# Pure_Noise.net
KiCad netlist of a schematic drawn in EAGLE
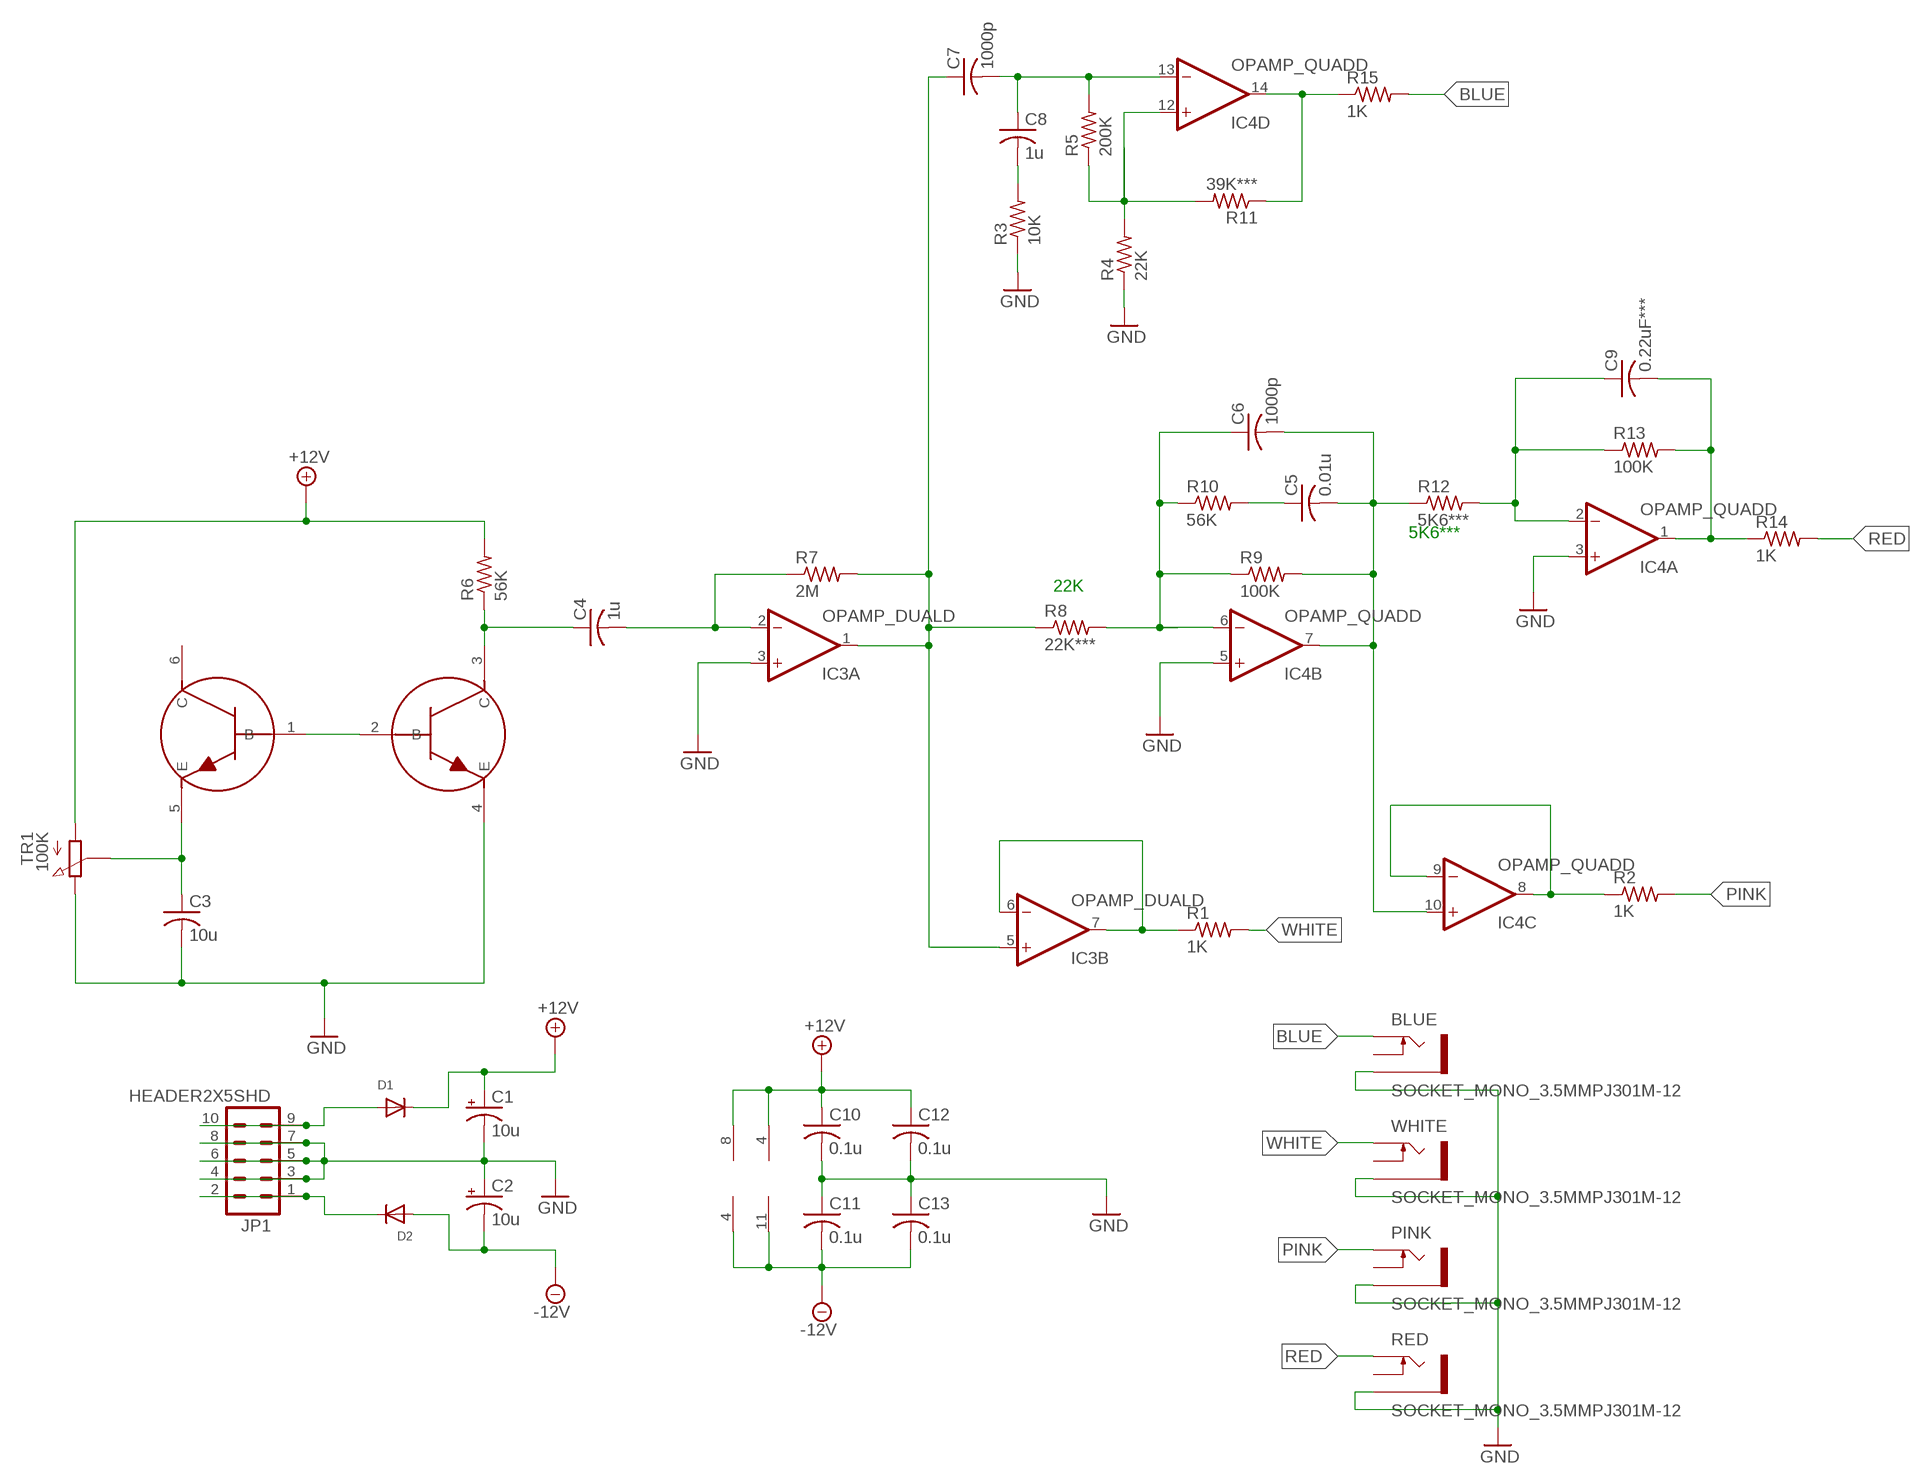
[diagram p0: schematic, sheet 1]

(export (version "E")
  (design (tool "Eeschema 10.0.6"))
  (components
    (comp (ref "BLUE")
      (value "SOCKET_MONO_3.5MMPJ301M-12")
      (footprint "eagle-import:PJ301M-12")
      (libsource (lib "eagle-import") (part "SOCKET_MONO_3.5MMPJ301M-12"))
    )
    (comp (ref "C1")
      (value "10u")
      (footprint "eagle-import:153CLV-0505")
      (libsource (lib "eagle-import") (part "CAPACITOR_POL-US153CLV-0505"))
    )
    (comp (ref "C2")
      (value "10u")
      (footprint "eagle-import:153CLV-0505")
      (libsource (lib "eagle-import") (part "CAPACITOR_POL-US153CLV-0505"))
    )
    (comp (ref "C3")
      (value "10u")
      (footprint "eagle-import:C0805")
      (libsource (lib "eagle-import") (part "CAPACITOR-USC0805"))
    )
    (comp (ref "C4")
      (value "1u")
      (footprint "eagle-import:C0805")
      (libsource (lib "eagle-import") (part "CAPACITOR-USC0805"))
    )
    (comp (ref "C5")
      (value "0.01u")
      (footprint "eagle-import:C0805")
      (libsource (lib "eagle-import") (part "CAPACITOR-USC0805"))
    )
    (comp (ref "C6")
      (value "1000p")
      (footprint "eagle-import:C0805")
      (libsource (lib "eagle-import") (part "CAPACITOR-USC0805"))
    )
    (comp (ref "C7")
      (value "1000p")
      (footprint "eagle-import:C0805")
      (libsource (lib "eagle-import") (part "CAPACITOR-USC0805"))
    )
    (comp (ref "C8")
      (value "1u")
      (footprint "eagle-import:C0805")
      (libsource (lib "eagle-import") (part "CAPACITOR-USC0805"))
    )
    (comp (ref "C9")
      (value "0.22uF***")
      (footprint "eagle-import:C0805")
      (libsource (lib "eagle-import") (part "CAPACITOR-USC0805"))
    )
    (comp (ref "C10")
      (value "0.1u")
      (footprint "eagle-import:C0805")
      (libsource (lib "eagle-import") (part "CAPACITOR-USC0805"))
    )
    (comp (ref "C11")
      (value "0.1u")
      (footprint "eagle-import:C0805")
      (libsource (lib "eagle-import") (part "CAPACITOR-USC0805"))
    )
    (comp (ref "C12")
      (value "0.1u")
      (footprint "eagle-import:C0805")
      (libsource (lib "eagle-import") (part "CAPACITOR-USC0805"))
    )
    (comp (ref "C13")
      (value "0.1u")
      (footprint "eagle-import:C0805")
      (libsource (lib "eagle-import") (part "CAPACITOR-USC0805"))
    )
    (comp (ref "D1")
      (value "DIODESMA")
      (footprint "eagle-import:SMADIODE")
      (libsource (lib "eagle-import") (part "DIODESMA"))
    )
    (comp (ref "D2")
      (value "DIODESMA")
      (footprint "eagle-import:SMADIODE")
      (libsource (lib "eagle-import") (part "DIODESMA"))
    )
    (comp (ref "IC3")
      (value "OPAMP_DUALD")
      (footprint "eagle-import:SO08")
      (libsource (lib "eagle-import") (part "OPAMP_DUALD"))
    )
    (comp (ref "IC4")
      (value "OPAMP_QUADD")
      (footprint "eagle-import:SO14")
      (libsource (lib "eagle-import") (part "OPAMP_QUADD"))
    )
    (comp (ref "JP1")
      (value "HEADER2X5SHD")
      (footprint "eagle-import:2X5-SHROUDED")
      (libsource (lib "eagle-import") (part "HEADER2X5SHD"))
    )
    (comp (ref "PINK")
      (value "SOCKET_MONO_3.5MMPJ301M-12")
      (footprint "eagle-import:PJ301M-12")
      (libsource (lib "eagle-import") (part "SOCKET_MONO_3.5MMPJ301M-12"))
    )
    (comp (ref "R1")
      (value "1K")
      (footprint "eagle-import:R0805")
      (libsource (lib "eagle-import") (part "RESISTOR_USR0805"))
    )
    (comp (ref "R2")
      (value "1K")
      (footprint "eagle-import:R0805")
      (libsource (lib "eagle-import") (part "RESISTOR_USR0805"))
    )
    (comp (ref "R3")
      (value "10K")
      (footprint "eagle-import:R0805")
      (libsource (lib "eagle-import") (part "RESISTOR_USR0805"))
    )
    (comp (ref "R4")
      (value "22K")
      (footprint "eagle-import:R0805")
      (libsource (lib "eagle-import") (part "RESISTOR_USR0805"))
    )
    (comp (ref "R5")
      (value "200K")
      (footprint "eagle-import:R0805")
      (libsource (lib "eagle-import") (part "RESISTOR_USR0805"))
    )
    (comp (ref "R6")
      (value "56K")
      (footprint "eagle-import:R0805")
      (libsource (lib "eagle-import") (part "RESISTOR_USR0805"))
    )
    (comp (ref "R7")
      (value "2M")
      (footprint "eagle-import:R0805")
      (libsource (lib "eagle-import") (part "RESISTOR_USR0805"))
    )
    (comp (ref "R8")
      (value "22K***")
      (footprint "eagle-import:R0805")
      (libsource (lib "eagle-import") (part "RESISTOR_USR0805"))
    )
    (comp (ref "R9")
      (value "100K")
      (footprint "eagle-import:R0805")
      (libsource (lib "eagle-import") (part "RESISTOR_USR0805"))
    )
    (comp (ref "R10")
      (value "56K")
      (footprint "eagle-import:R0805")
      (libsource (lib "eagle-import") (part "RESISTOR_USR0805"))
    )
    (comp (ref "R11")
      (value "39K***")
      (footprint "eagle-import:R0805")
      (libsource (lib "eagle-import") (part "RESISTOR_USR0805"))
    )
    (comp (ref "R12")
      (value "5K6***")
      (footprint "eagle-import:R0805")
      (libsource (lib "eagle-import") (part "RESISTOR_USR0805"))
    )
    (comp (ref "R13")
      (value "100K")
      (footprint "eagle-import:R0805")
      (libsource (lib "eagle-import") (part "RESISTOR_USR0805"))
    )
    (comp (ref "R14")
      (value "1K")
      (footprint "eagle-import:R0805")
      (libsource (lib "eagle-import") (part "RESISTOR_USR0805"))
    )
    (comp (ref "R15")
      (value "1K")
      (footprint "eagle-import:R0805")
      (libsource (lib "eagle-import") (part "RESISTOR_USR0805"))
    )
    (comp (ref "RED")
      (value "SOCKET_MONO_3.5MMPJ301M-12")
      (footprint "eagle-import:PJ301M-12")
      (libsource (lib "eagle-import") (part "SOCKET_MONO_3.5MMPJ301M-12"))
    )
    (comp (ref "T1")
      (value "TRANSISTOR_PAIR_NPN")
      (footprint "eagle-import:TRANS_PAIR")
      (libsource (lib "eagle-import") (part "TRANSISTOR_PAIR_NPN"))
    )
    (comp (ref "TR1")
      (value "100K")
      (footprint "eagle-import:TRIMMER_TH")
      (libsource (lib "eagle-import") (part "RESISTOR_VARIABLETRIMMER_TH"))
    )
    (comp (ref "WHITE")
      (value "SOCKET_MONO_3.5MMPJ301M-12")
      (footprint "eagle-import:PJ301M-12")
      (libsource (lib "eagle-import") (part "SOCKET_MONO_3.5MMPJ301M-12"))
    )
  )
  (nets
    (net (code "1") (name "+12V") (class "Default")
      (node (ref "C1") (pin "+") (pinfunction "+_+") (pintype "passive"))
      (node (ref "C10") (pin "1") (pinfunction "1_1") (pintype "passive"))
      (node (ref "C12") (pin "1") (pinfunction "1_1") (pintype "passive"))
      (node (ref "D1") (pin "C") (pinfunction "C_C") (pintype "passive"))
      (node (ref "IC3") (pin "8") (pinfunction "V+_8") (pintype "power_in"))
      (node (ref "IC4") (pin "4") (pinfunction "V+_4") (pintype "power_in"))
      (node (ref "R6") (pin "2") (pinfunction "2_2") (pintype "passive"))
      (node (ref "TR1") (pin "1") (pinfunction "1_1") (pintype "passive"))
    )
    (net (code "2") (name "-12V") (class "Default")
      (node (ref "C11") (pin "2") (pinfunction "2_2") (pintype "passive"))
      (node (ref "C13") (pin "2") (pinfunction "2_2") (pintype "passive"))
      (node (ref "C2") (pin "-") (pinfunction "-_-") (pintype "passive"))
      (node (ref "D2") (pin "A") (pinfunction "A_A") (pintype "passive"))
      (node (ref "IC3") (pin "4") (pinfunction "V-_4") (pintype "power_in"))
      (node (ref "IC4") (pin "11") (pinfunction "V-_11") (pintype "power_in"))
    )
    (net (code "3") (name "BLUE") (class "Default")
      (node (ref "BLUE") (pin "TIP") (pinfunction "TIP_TIP") (pintype "passive"))
      (node (ref "R15") (pin "2") (pinfunction "2_2") (pintype "passive"))
    )
    (net (code "4") (name "GND") (class "Default")
      (node (ref "BLUE") (pin "GND") (pinfunction "SLEEVE_GND") (pintype "passive"))
      (node (ref "C1") (pin "-") (pinfunction "-_-") (pintype "passive"))
      (node (ref "C10") (pin "2") (pinfunction "2_2") (pintype "passive"))
      (node (ref "C11") (pin "1") (pinfunction "1_1") (pintype "passive"))
      (node (ref "C12") (pin "2") (pinfunction "2_2") (pintype "passive"))
      (node (ref "C13") (pin "1") (pinfunction "1_1") (pintype "passive"))
      (node (ref "C2") (pin "+") (pinfunction "+_+") (pintype "passive"))
      (node (ref "C3") (pin "2") (pinfunction "2_2") (pintype "passive"))
      (node (ref "IC3") (pin "3") (pinfunction "+IN_3") (pintype "input"))
      (node (ref "IC4") (pin "3") (pinfunction "+IN_3") (pintype "input"))
      (node (ref "IC4") (pin "5") (pinfunction "+IN_5") (pintype "input"))
      (node (ref "JP1") (pin "3") (pinfunction "3_3") (pintype "passive"))
      (node (ref "JP1") (pin "4") (pinfunction "4_4") (pintype "passive"))
      (node (ref "JP1") (pin "5") (pinfunction "5_5") (pintype "passive"))
      (node (ref "JP1") (pin "6") (pinfunction "6_6") (pintype "passive"))
      (node (ref "JP1") (pin "7") (pinfunction "7_7") (pintype "passive"))
      (node (ref "JP1") (pin "8") (pinfunction "8_8") (pintype "passive"))
      (node (ref "PINK") (pin "GND") (pinfunction "SLEEVE_GND") (pintype "passive"))
      (node (ref "R3") (pin "1") (pinfunction "1_1") (pintype "passive"))
      (node (ref "R4") (pin "1") (pinfunction "1_1") (pintype "passive"))
      (node (ref "RED") (pin "GND") (pinfunction "SLEEVE_GND") (pintype "passive"))
      (node (ref "T1") (pin "4") (pinfunction "E_4") (pintype "bidirectional"))
      (node (ref "TR1") (pin "3") (pinfunction "3_3") (pintype "passive"))
      (node (ref "WHITE") (pin "GND") (pinfunction "SLEEVE_GND") (pintype "passive"))
    )
    (net (code "5") (name "Net-(C5-Pad1)") (class "Default")
      (node (ref "C5") (pin "1") (pinfunction "1_1") (pintype "passive"))
      (node (ref "R10") (pin "2") (pinfunction "2_2") (pintype "passive"))
    )
    (net (code "6") (name "Net-(C8-Pad2)") (class "Default")
      (node (ref "C8") (pin "2") (pinfunction "2_2") (pintype "passive"))
      (node (ref "R3") (pin "2") (pinfunction "2_2") (pintype "passive"))
    )
    (net (code "7") (name "Net-(D1-PadA)") (class "Default")
      (node (ref "D1") (pin "A") (pinfunction "A_A") (pintype "passive"))
      (node (ref "JP1") (pin "10") (pinfunction "10_10") (pintype "passive"))
      (node (ref "JP1") (pin "9") (pinfunction "9_9") (pintype "passive"))
    )
    (net (code "8") (name "Net-(D2-PadC)") (class "Default")
      (node (ref "D2") (pin "C") (pinfunction "C_C") (pintype "passive"))
      (node (ref "JP1") (pin "1") (pinfunction "1_1") (pintype "passive"))
      (node (ref "JP1") (pin "2") (pinfunction "2_2") (pintype "passive"))
    )
    (net (code "9") (name "Net-(IC3A--IN)") (class "Default")
      (node (ref "C4") (pin "2") (pinfunction "2_2") (pintype "passive"))
      (node (ref "IC3") (pin "2") (pinfunction "-IN_2") (pintype "input"))
      (node (ref "R7") (pin "1") (pinfunction "1_1") (pintype "passive"))
    )
    (net (code "10") (name "Net-(IC3A-OUT)") (class "Default")
      (node (ref "C7") (pin "1") (pinfunction "1_1") (pintype "passive"))
      (node (ref "IC3") (pin "1") (pinfunction "OUT_1") (pintype "output"))
      (node (ref "IC3") (pin "5") (pinfunction "+IN_5") (pintype "input"))
      (node (ref "R7") (pin "2") (pinfunction "2_2") (pintype "passive"))
      (node (ref "R8") (pin "1") (pinfunction "1_1") (pintype "passive"))
    )
    (net (code "11") (name "Net-(IC3B--IN)") (class "Default")
      (node (ref "IC3") (pin "6") (pinfunction "-IN_6") (pintype "input"))
      (node (ref "IC3") (pin "7") (pinfunction "OUT_7") (pintype "output"))
      (node (ref "R1") (pin "1") (pinfunction "1_1") (pintype "passive"))
    )
    (net (code "12") (name "Net-(IC4A--IN)") (class "Default")
      (node (ref "C9") (pin "1") (pinfunction "1_1") (pintype "passive"))
      (node (ref "IC4") (pin "2") (pinfunction "-IN_2") (pintype "input"))
      (node (ref "R12") (pin "2") (pinfunction "2_2") (pintype "passive"))
      (node (ref "R13") (pin "1") (pinfunction "1_1") (pintype "passive"))
    )
    (net (code "13") (name "Net-(IC4A-OUT)") (class "Default")
      (node (ref "C9") (pin "2") (pinfunction "2_2") (pintype "passive"))
      (node (ref "IC4") (pin "1") (pinfunction "OUT_1") (pintype "output"))
      (node (ref "R13") (pin "2") (pinfunction "2_2") (pintype "passive"))
      (node (ref "R14") (pin "1") (pinfunction "1_1") (pintype "passive"))
    )
    (net (code "14") (name "Net-(IC4B--IN)") (class "Default")
      (node (ref "C6") (pin "1") (pinfunction "1_1") (pintype "passive"))
      (node (ref "IC4") (pin "6") (pinfunction "-IN_6") (pintype "input"))
      (node (ref "R10") (pin "1") (pinfunction "1_1") (pintype "passive"))
      (node (ref "R8") (pin "2") (pinfunction "2_2") (pintype "passive"))
      (node (ref "R9") (pin "1") (pinfunction "1_1") (pintype "passive"))
    )
    (net (code "15") (name "Net-(IC4B-OUT)") (class "Default")
      (node (ref "C5") (pin "2") (pinfunction "2_2") (pintype "passive"))
      (node (ref "C6") (pin "2") (pinfunction "2_2") (pintype "passive"))
      (node (ref "IC4") (pin "10") (pinfunction "+IN_10") (pintype "input"))
      (node (ref "IC4") (pin "7") (pinfunction "OUT_7") (pintype "output"))
      (node (ref "R12") (pin "1") (pinfunction "1_1") (pintype "passive"))
      (node (ref "R9") (pin "2") (pinfunction "2_2") (pintype "passive"))
    )
    (net (code "16") (name "Net-(IC4C--IN)") (class "Default")
      (node (ref "IC4") (pin "8") (pinfunction "OUT_8") (pintype "output"))
      (node (ref "IC4") (pin "9") (pinfunction "-IN_9") (pintype "input"))
      (node (ref "R2") (pin "1") (pinfunction "1_1") (pintype "passive"))
    )
    (net (code "17") (name "Net-(IC4D-+IN)") (class "Default")
      (node (ref "IC4") (pin "12") (pinfunction "+IN_12") (pintype "input"))
      (node (ref "R11") (pin "2") (pinfunction "2_2") (pintype "passive"))
      (node (ref "R4") (pin "2") (pinfunction "2_2") (pintype "passive"))
      (node (ref "R5") (pin "1") (pinfunction "1_1") (pintype "passive"))
    )
    (net (code "18") (name "Net-(IC4D--IN)") (class "Default")
      (node (ref "C7") (pin "2") (pinfunction "2_2") (pintype "passive"))
      (node (ref "C8") (pin "1") (pinfunction "1_1") (pintype "passive"))
      (node (ref "IC4") (pin "13") (pinfunction "-IN_13") (pintype "input"))
      (node (ref "R5") (pin "2") (pinfunction "2_2") (pintype "passive"))
    )
    (net (code "19") (name "Net-(IC4D-OUT)") (class "Default")
      (node (ref "IC4") (pin "14") (pinfunction "OUT_14") (pintype "output"))
      (node (ref "R11") (pin "1") (pinfunction "1_1") (pintype "passive"))
      (node (ref "R15") (pin "1") (pinfunction "1_1") (pintype "passive"))
    )
    (net (code "20") (name "Net-(T1A-B)") (class "Default")
      (node (ref "T1") (pin "1") (pinfunction "B_1") (pintype "bidirectional"))
      (node (ref "T1") (pin "2") (pinfunction "B_2") (pintype "bidirectional"))
    )
    (net (code "21") (name "Net-(T1A-C)") (class "Default")
      (node (ref "C4") (pin "1") (pinfunction "1_1") (pintype "passive"))
      (node (ref "R6") (pin "1") (pinfunction "1_1") (pintype "passive"))
      (node (ref "T1") (pin "3") (pinfunction "C_3") (pintype "bidirectional"))
    )
    (net (code "22") (name "Net-(T1B-E)") (class "Default")
      (node (ref "C3") (pin "1") (pinfunction "1_1") (pintype "passive"))
      (node (ref "T1") (pin "5") (pinfunction "E_5") (pintype "bidirectional"))
      (node (ref "TR1") (pin "2") (pinfunction "2_2") (pintype "passive"))
    )
    (net (code "23") (name "PINK") (class "Default")
      (node (ref "PINK") (pin "TIP") (pinfunction "TIP_TIP") (pintype "passive"))
      (node (ref "R2") (pin "2") (pinfunction "2_2") (pintype "passive"))
    )
    (net (code "24") (name "RED") (class "Default")
      (node (ref "R14") (pin "2") (pinfunction "2_2") (pintype "passive"))
      (node (ref "RED") (pin "TIP") (pinfunction "TIP_TIP") (pintype "passive"))
    )
    (net (code "25") (name "WHITE") (class "Default")
      (node (ref "R1") (pin "2") (pinfunction "2_2") (pintype "passive"))
      (node (ref "WHITE") (pin "TIP") (pinfunction "TIP_TIP") (pintype "passive"))
    )
    (net (code "26") (name "unconnected-(BLUE-SWITCH-PadNORM)") (class "Default")
      (node (ref "BLUE") (pin "NORM") (pinfunction "SWITCH_NORM") (pintype "passive"))
    )
    (net (code "27") (name "unconnected-(PINK-SWITCH-PadNORM)") (class "Default")
      (node (ref "PINK") (pin "NORM") (pinfunction "SWITCH_NORM") (pintype "passive"))
    )
    (net (code "28") (name "unconnected-(RED-SWITCH-PadNORM)") (class "Default")
      (node (ref "RED") (pin "NORM") (pinfunction "SWITCH_NORM") (pintype "passive"))
    )
    (net (code "29") (name "unconnected-(T1B-C-Pad6)") (class "Default")
      (node (ref "T1") (pin "6") (pinfunction "C_6") (pintype "bidirectional"))
    )
    (net (code "30") (name "unconnected-(WHITE-SWITCH-PadNORM)") (class "Default")
      (node (ref "WHITE") (pin "NORM") (pinfunction "SWITCH_NORM") (pintype "passive"))
    )
  )
)
